# Sheet1.net
KiCad netlist of a schematic drawn in Altium Designer
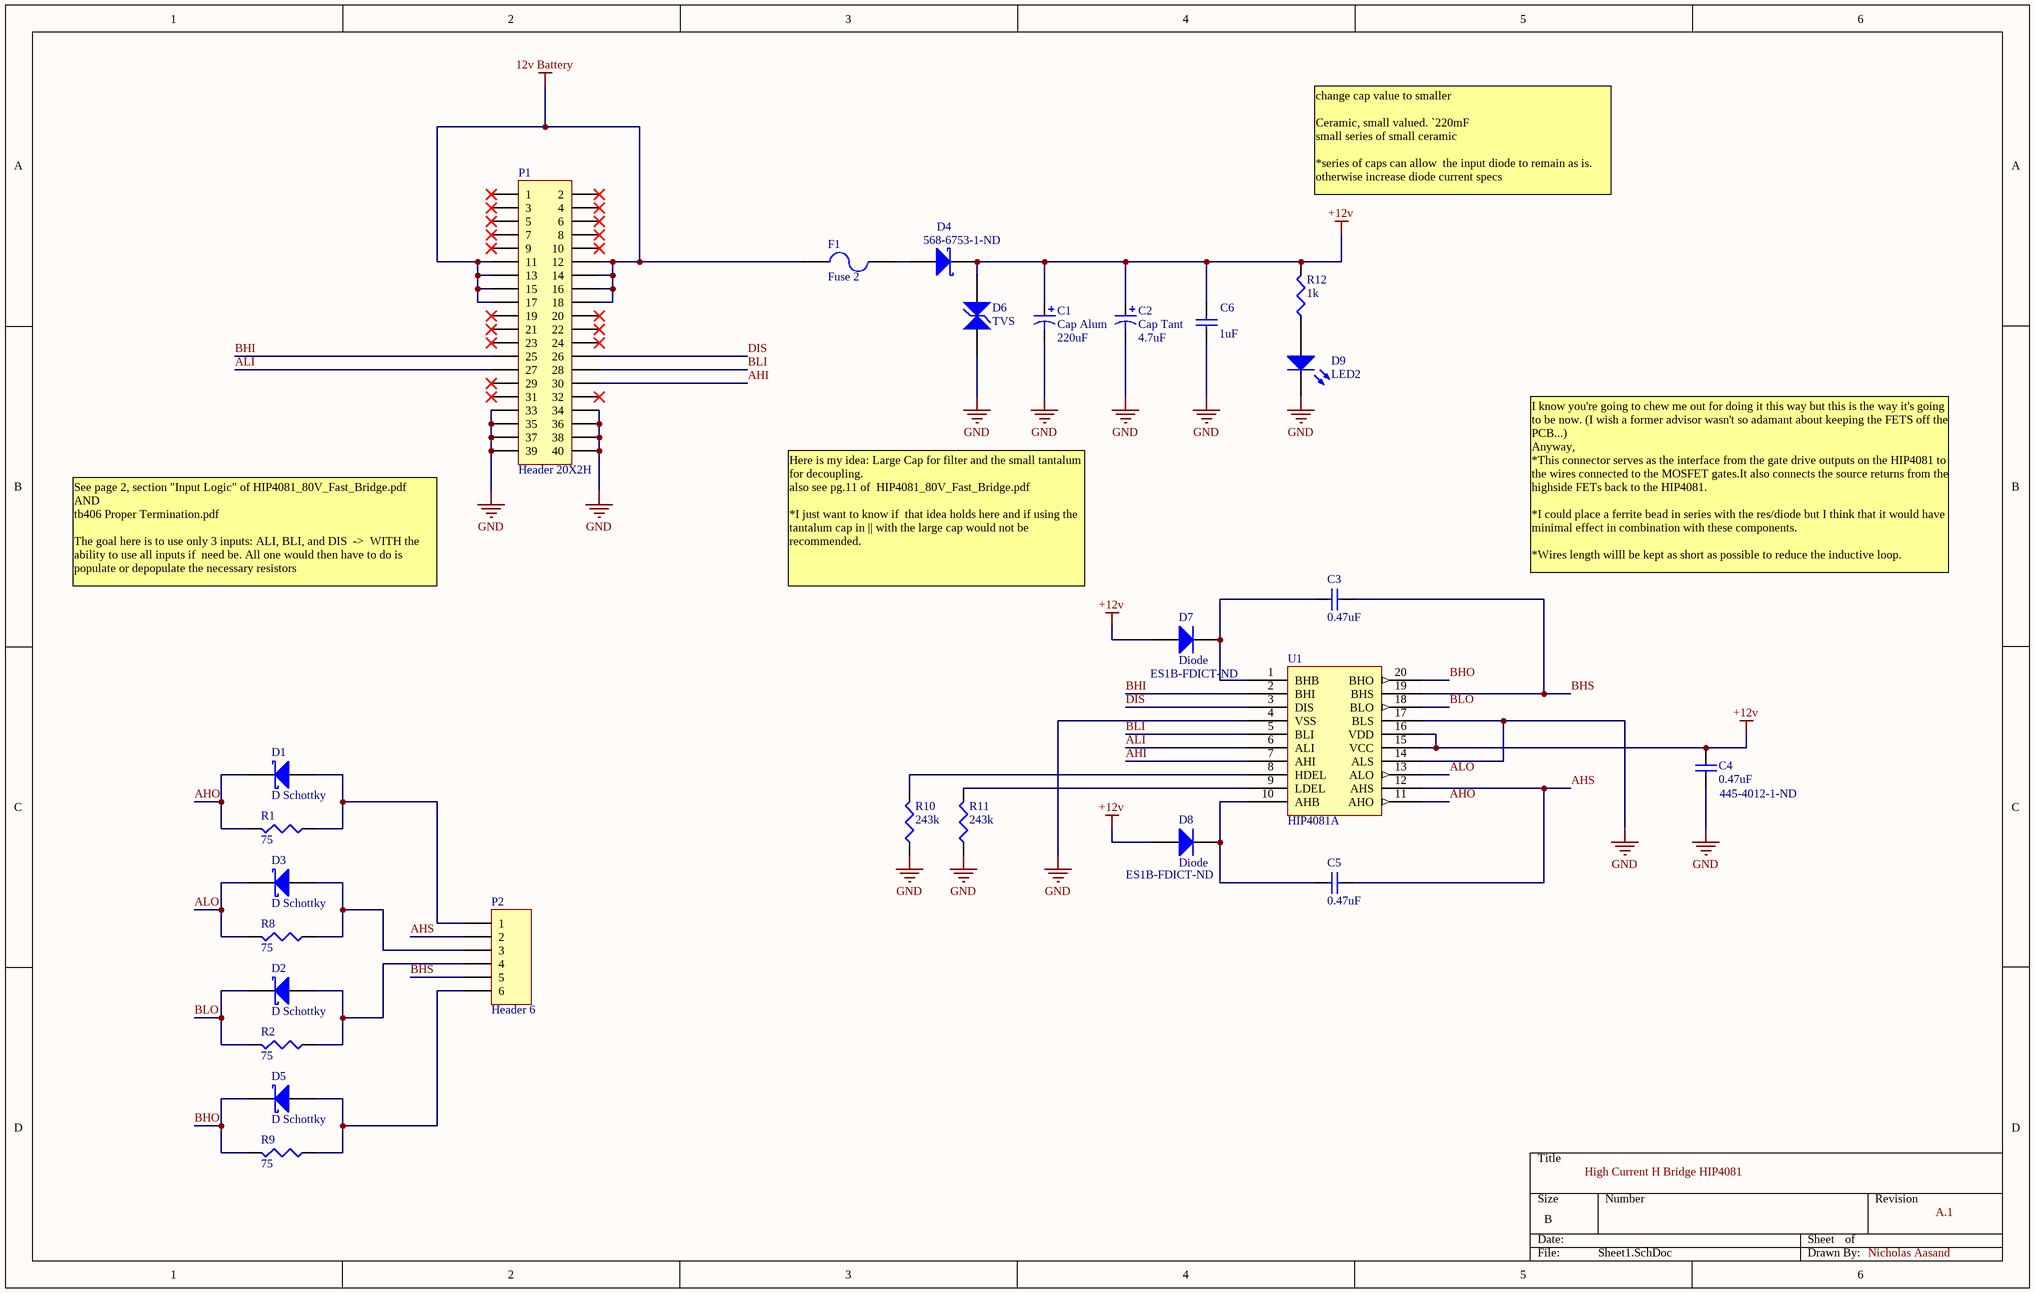
[diagram p0: Sheet1.SchDoc]

(export (version "E")
  (design (tool "Eeschema 10.0.6"))
  (components
    (comp (ref "C1")
      (value "Cap Alum")
      (footprint "CAPPR3.5-8x11.5")
      (description "Polarized Capacitor (Radial)")
      (fields (field (name "ALTIUM_VALUE") "220uF") (field (name "PUBLISHER") "Altium Limited"))
      (libsource (lib "Miscellaneous Devices") (part "Cap Pol1"))
    )
    (comp (ref "C2")
      (value "Cap Tant")
      (footprint "CP1206")
      (description "Polarized Capacitor (Surface Mount)")
      (fields (field (name "ALTIUM_VALUE") "4.7uF") (field (name "PUBLISHER") "Altium Limited"))
      (libsource (lib "Miscellaneous Devices") (part "Cap Pol3"))
    )
    (comp (ref "C3")
      (value "0.47uF")
      (footprint "C0805")
      (description "Capacitor (Semiconductor SIM Model)")
      (fields (field (name "Comment") "0805") (field (name "PUBLISHER") "Altium Limited"))
      (libsource (lib "Miscellaneous Devices") (part "Cap Semi"))
    )
    (comp (ref "C4")
      (value "0.47uF")
      (footprint "C1206")
      (description "Capacitor (Semiconductor SIM Model)")
      (fields
        (field (name "DIGIKEY") "445-4012-1-ND")
        (field (name "Comment") "0805")
        (field (name "PUBLISHER") "Altium Limited")
      )
      (libsource (lib "Miscellaneous Devices") (part "Cap Semi"))
    )
    (comp (ref "C5")
      (value "0.47uF")
      (footprint "C0805")
      (description "Capacitor (Semiconductor SIM Model)")
      (fields (field (name "Comment") "0805") (field (name "PUBLISHER") "Altium Limited"))
      (libsource (lib "Miscellaneous Devices") (part "Cap Semi"))
    )
    (comp (ref "C6")
      (value "1uF")
      (footprint "C0805")
      (description "Capacitor (Semiconductor SIM Model)")
      (fields (field (name "Comment") "0805") (field (name "PUBLISHER") "Altium Limited"))
      (libsource (lib "Miscellaneous Devices") (part "Cap Semi"))
    )
    (comp (ref "D1")
      (value "D Schottky")
      (footprint "SMB")
      (description "Schottky Diode")
      (fields (field (name "PUBLISHER") "Altium Limited"))
      (libsource (lib "Miscellaneous Devices") (part "D Schottky"))
    )
    (comp (ref "D2")
      (value "D Schottky")
      (footprint "SMB")
      (description "Schottky Diode")
      (fields (field (name "PUBLISHER") "Altium Limited"))
      (libsource (lib "Miscellaneous Devices") (part "D Schottky"))
    )
    (comp (ref "D3")
      (value "D Schottky")
      (footprint "SMB")
      (description "Schottky Diode")
      (fields (field (name "PUBLISHER") "Altium Limited"))
      (libsource (lib "Miscellaneous Devices") (part "D Schottky"))
    )
    (comp (ref "D4")
      (value "PMEG3030EP,115")
      (footprint "SOD128")
      (fields (field (name "DIGIKEY") "568-6753-1-ND") (field (name "PUBLISHER") "Altium Limited"))
      (libsource (lib "Miscellaneous Devices") (part "D Schottky"))
    )
    (comp (ref "D5")
      (value "D Schottky")
      (footprint "SMB")
      (description "Schottky Diode")
      (fields (field (name "PUBLISHER") "Altium Limited"))
      (libsource (lib "Miscellaneous Devices") (part "D Schottky"))
    )
    (comp (ref "D6")
      (value "TVS")
      (footprint "DSO-C2/X3.3")
      (description "Bi-directional TVS diode")
      (libsource (lib "Chips") (part "TVS_Bi"))
    )
    (comp (ref "D7")
      (value "Diode")
      (footprint "DSO-C2/G1.6")
      (description "Default Diode")
      (fields (field (name "DIGIKEY") "ES1B-FDICT-ND") (field (name "PUBLISHER") "Altium Limited"))
      (libsource (lib "Miscellaneous Devices") (part "Diode"))
    )
    (comp (ref "D8")
      (value "Diode")
      (footprint "DSO-C2/G1.6")
      (description "Default Diode")
      (fields (field (name "DIGIKEY") "ES1B-FDICT-ND") (field (name "PUBLISHER") "Altium Limited"))
      (libsource (lib "Miscellaneous Devices") (part "Diode"))
    )
    (comp (ref "D9")
      (value "LED2")
      (footprint "C0805")
      (description "Ultra Bright YELLOW ORANGE AlInGaP LED")
      (fields (field (name "PUBLISHER") "Altium Limited"))
      (libsource (lib "Miscellaneous Devices") (part "LED2"))
    )
    (comp (ref "F1")
      (value "Fuse 2")
      (footprint "3550-2 ATC Fuse Holder")
      (description "Fuse")
      (fields (field (name "PUBLISHER") "Altium Limited"))
      (libsource (lib "Miscellaneous Devices") (part "Fuse 2"))
    )
    (comp (ref "P1")
      (value "Header 20X2H")
      (footprint "HDR2X20H")
      (description "Header, 20-Pin, Dual row, Right Angle")
      (fields (field (name "PUBLISHER") "Altium Limited"))
      (libsource (lib "Miscellaneous Connectors") (part "Header 20X2H"))
    )
    (comp (ref "P2")
      (value "Header 6")
      (footprint "B6PS-VH")
      (description "Header, 6-Pin")
      (fields (field (name "PUBLISHER") "Altium Limited"))
      (libsource (lib "Miscellaneous Connectors") (part "Header 6"))
    )
    (comp (ref "R1")
      (value "75")
      (footprint "RESC3216N")
      (description "Resistor")
      (fields (field (name "Comment") "1206"))
      (libsource (lib "Miscellaneous Devices") (part "Res3"))
    )
    (comp (ref "R2")
      (value "75")
      (footprint "RESC3216N")
      (description "Resistor")
      (fields (field (name "Comment") "1206"))
      (libsource (lib "Miscellaneous Devices") (part "Res3"))
    )
    (comp (ref "R8")
      (value "75")
      (footprint "RESC3216N")
      (description "Resistor")
      (fields (field (name "Comment") "1206"))
      (libsource (lib "Miscellaneous Devices") (part "Res3"))
    )
    (comp (ref "R9")
      (value "75")
      (footprint "RESC3216N")
      (description "Resistor")
      (fields (field (name "Comment") "1206"))
      (libsource (lib "Miscellaneous Devices") (part "Res3"))
    )
    (comp (ref "R10")
      (value "243k")
      (footprint "C1206")
      (description "Resistor")
      (fields (field (name "Comment") "1206"))
      (libsource (lib "Miscellaneous Devices") (part "Res3"))
    )
    (comp (ref "R11")
      (value "243k")
      (footprint "C1206")
      (description "Resistor")
      (fields (field (name "Comment") "1206"))
      (libsource (lib "Miscellaneous Devices") (part "Res3"))
    )
    (comp (ref "R12")
      (value "1k")
      (footprint "RESC3216N")
      (description "Resistor")
      (fields (field (name "Comment") "1206"))
      (libsource (lib "Miscellaneous Devices") (part "Res3"))
    )
    (comp (ref "U1")
      (value "HIP4081A")
      (footprint "SOIC127P1030-20M")
      (description "80V/2.5A Peak, High Frequency Full Bridge FET Driver")
      (libsource (lib "HIP4081A") (part "HIP4081A"))
    )
  )
  (nets
    (net (code "1") (name "+12v") (class "Default")
      (node (ref "C1") (pin "1") (pinfunction "1_1") (pintype "passive"))
      (node (ref "C2") (pin "1") (pinfunction "1_1") (pintype "passive"))
      (node (ref "C4") (pin "1") (pinfunction "1_1") (pintype "passive"))
      (node (ref "C6") (pin "2") (pinfunction "2_2") (pintype "passive"))
      (node (ref "D4") (pin "2") (pinfunction "K_2") (pintype "passive"))
      (node (ref "D6") (pin "1") (pinfunction "1_1") (pintype "passive"))
      (node (ref "D7") (pin "1") (pinfunction "A_1") (pintype "passive"))
      (node (ref "D8") (pin "1") (pinfunction "A_1") (pintype "passive"))
      (node (ref "R12") (pin "2") (pinfunction "2_2") (pintype "passive"))
      (node (ref "U1") (pin "15") (pinfunction "VCC_15") (pintype "passive"))
      (node (ref "U1") (pin "16") (pinfunction "VDD_16") (pintype "passive"))
    )
    (net (code "2") (name "/AHI") (class "Default")
      (node (ref "P1") (pin "30") (pinfunction "30_30") (pintype "passive"))
      (node (ref "U1") (pin "7") (pinfunction "AHI_7") (pintype "passive"))
    )
    (net (code "3") (name "/AHO") (class "Default")
      (node (ref "D1") (pin "2") (pinfunction "K_2") (pintype "passive"))
      (node (ref "R1") (pin "2") (pinfunction "2_2") (pintype "passive"))
      (node (ref "U1") (pin "11") (pinfunction "AHO_11") (pintype "output"))
    )
    (net (code "4") (name "/AHS") (class "Default")
      (node (ref "C5") (pin "1") (pinfunction "1_1") (pintype "passive"))
      (node (ref "P2") (pin "2") (pinfunction "2_2") (pintype "passive"))
      (node (ref "U1") (pin "12") (pinfunction "AHS_12") (pintype "passive"))
    )
    (net (code "5") (name "/ALI") (class "Default")
      (node (ref "P1") (pin "27") (pinfunction "27_27") (pintype "passive"))
      (node (ref "U1") (pin "6") (pinfunction "ALI_6") (pintype "passive"))
    )
    (net (code "6") (name "/ALO") (class "Default")
      (node (ref "D3") (pin "2") (pinfunction "K_2") (pintype "passive"))
      (node (ref "R8") (pin "2") (pinfunction "2_2") (pintype "passive"))
      (node (ref "U1") (pin "13") (pinfunction "ALO_13") (pintype "output"))
    )
    (net (code "7") (name "/BHI") (class "Default")
      (node (ref "P1") (pin "25") (pinfunction "25_25") (pintype "passive"))
      (node (ref "U1") (pin "2") (pinfunction "BHI_2") (pintype "passive"))
    )
    (net (code "8") (name "/BHO") (class "Default")
      (node (ref "D5") (pin "2") (pinfunction "K_2") (pintype "passive"))
      (node (ref "R9") (pin "2") (pinfunction "2_2") (pintype "passive"))
      (node (ref "U1") (pin "20") (pinfunction "BHO_20") (pintype "output"))
    )
    (net (code "9") (name "/BHS") (class "Default")
      (node (ref "C3") (pin "1") (pinfunction "1_1") (pintype "passive"))
      (node (ref "P2") (pin "5") (pinfunction "5_5") (pintype "passive"))
      (node (ref "U1") (pin "19") (pinfunction "BHS_19") (pintype "passive"))
    )
    (net (code "10") (name "/BLI") (class "Default")
      (node (ref "P1") (pin "28") (pinfunction "28_28") (pintype "passive"))
      (node (ref "U1") (pin "5") (pinfunction "BLI_5") (pintype "passive"))
    )
    (net (code "11") (name "/BLO") (class "Default")
      (node (ref "D2") (pin "2") (pinfunction "K_2") (pintype "passive"))
      (node (ref "R2") (pin "2") (pinfunction "2_2") (pintype "passive"))
      (node (ref "U1") (pin "18") (pinfunction "BLO_18") (pintype "output"))
    )
    (net (code "12") (name "/DIS") (class "Default")
      (node (ref "P1") (pin "26") (pinfunction "26_26") (pintype "passive"))
      (node (ref "U1") (pin "3") (pinfunction "DIS_3") (pintype "passive"))
    )
    (net (code "13") (name "12v Battery") (class "Default")
      (node (ref "F1") (pin "1") (pinfunction "1_1") (pintype "passive"))
      (node (ref "P1") (pin "11") (pinfunction "11_11") (pintype "passive"))
      (node (ref "P1") (pin "12") (pinfunction "12_12") (pintype "passive"))
      (node (ref "P1") (pin "13") (pinfunction "13_13") (pintype "passive"))
      (node (ref "P1") (pin "14") (pinfunction "14_14") (pintype "passive"))
      (node (ref "P1") (pin "15") (pinfunction "15_15") (pintype "passive"))
      (node (ref "P1") (pin "16") (pinfunction "16_16") (pintype "passive"))
      (node (ref "P1") (pin "17") (pinfunction "17_17") (pintype "passive"))
      (node (ref "P1") (pin "18") (pinfunction "18_18") (pintype "passive"))
    )
    (net (code "14") (name "GND") (class "Default")
      (node (ref "C1") (pin "2") (pinfunction "2_2") (pintype "passive"))
      (node (ref "C2") (pin "2") (pinfunction "2_2") (pintype "passive"))
      (node (ref "C4") (pin "2") (pinfunction "2_2") (pintype "passive"))
      (node (ref "C6") (pin "1") (pinfunction "1_1") (pintype "passive"))
      (node (ref "D6") (pin "2") (pinfunction "2_2") (pintype "passive"))
      (node (ref "D9") (pin "2") (pinfunction "K_2") (pintype "passive"))
      (node (ref "P1") (pin "33") (pinfunction "33_33") (pintype "passive"))
      (node (ref "P1") (pin "34") (pinfunction "34_34") (pintype "passive"))
      (node (ref "P1") (pin "35") (pinfunction "35_35") (pintype "passive"))
      (node (ref "P1") (pin "36") (pinfunction "36_36") (pintype "passive"))
      (node (ref "P1") (pin "37") (pinfunction "37_37") (pintype "passive"))
      (node (ref "P1") (pin "38") (pinfunction "38_38") (pintype "passive"))
      (node (ref "P1") (pin "39") (pinfunction "39_39") (pintype "passive"))
      (node (ref "P1") (pin "40") (pinfunction "40_40") (pintype "passive"))
      (node (ref "R10") (pin "1") (pinfunction "1_1") (pintype "passive"))
      (node (ref "R11") (pin "1") (pinfunction "1_1") (pintype "passive"))
      (node (ref "U1") (pin "14") (pinfunction "ALS_14") (pintype "passive"))
      (node (ref "U1") (pin "17") (pinfunction "BLS_17") (pintype "passive"))
      (node (ref "U1") (pin "4") (pinfunction "VSS_4") (pintype "power_in"))
    )
    (net (code "15") (name "Net-(D1-A)") (class "Default")
      (node (ref "D1") (pin "1") (pinfunction "A_1") (pintype "passive"))
      (node (ref "P2") (pin "1") (pinfunction "1_1") (pintype "passive"))
      (node (ref "R1") (pin "1") (pinfunction "1_1") (pintype "passive"))
    )
    (net (code "16") (name "Net-(D2-A)") (class "Default")
      (node (ref "D2") (pin "1") (pinfunction "A_1") (pintype "passive"))
      (node (ref "P2") (pin "4") (pinfunction "4_4") (pintype "passive"))
      (node (ref "R2") (pin "1") (pinfunction "1_1") (pintype "passive"))
    )
    (net (code "17") (name "Net-(D3-A)") (class "Default")
      (node (ref "D3") (pin "1") (pinfunction "A_1") (pintype "passive"))
      (node (ref "P2") (pin "3") (pinfunction "3_3") (pintype "passive"))
      (node (ref "R8") (pin "1") (pinfunction "1_1") (pintype "passive"))
    )
    (net (code "18") (name "Net-(D4-A)") (class "Default")
      (node (ref "D4") (pin "1") (pinfunction "A_1") (pintype "passive"))
      (node (ref "F1") (pin "2") (pinfunction "2_2") (pintype "passive"))
    )
    (net (code "19") (name "Net-(D5-A)") (class "Default")
      (node (ref "D5") (pin "1") (pinfunction "A_1") (pintype "passive"))
      (node (ref "P2") (pin "6") (pinfunction "6_6") (pintype "passive"))
      (node (ref "R9") (pin "1") (pinfunction "1_1") (pintype "passive"))
    )
    (net (code "20") (name "Net-(D7-K)") (class "Default")
      (node (ref "C3") (pin "2") (pinfunction "2_2") (pintype "passive"))
      (node (ref "D7") (pin "2") (pinfunction "K_2") (pintype "passive"))
      (node (ref "U1") (pin "1") (pinfunction "BHB_1") (pintype "passive"))
    )
    (net (code "21") (name "Net-(D8-K)") (class "Default")
      (node (ref "C5") (pin "2") (pinfunction "2_2") (pintype "passive"))
      (node (ref "D8") (pin "2") (pinfunction "K_2") (pintype "passive"))
      (node (ref "U1") (pin "10") (pinfunction "AHB_10") (pintype "passive"))
    )
    (net (code "22") (name "Net-(D9-A)") (class "Default")
      (node (ref "D9") (pin "1") (pinfunction "A_1") (pintype "passive"))
      (node (ref "R12") (pin "1") (pinfunction "1_1") (pintype "passive"))
    )
    (net (code "23") (name "Net-(U1-HDEL)") (class "Default")
      (node (ref "R10") (pin "2") (pinfunction "2_2") (pintype "passive"))
      (node (ref "U1") (pin "8") (pinfunction "HDEL_8") (pintype "passive"))
    )
    (net (code "24") (name "Net-(U1-LDEL)") (class "Default")
      (node (ref "R11") (pin "2") (pinfunction "2_2") (pintype "passive"))
      (node (ref "U1") (pin "9") (pinfunction "LDEL_9") (pintype "passive"))
    )
    (net (code "25") (name "unconnected-(P1-Pad1)") (class "Default")
      (node (ref "P1") (pin "1") (pinfunction "1_1") (pintype "passive+no_connect"))
    )
    (net (code "26") (name "unconnected-(P1-Pad2)") (class "Default")
      (node (ref "P1") (pin "2") (pinfunction "2_2") (pintype "passive+no_connect"))
    )
    (net (code "27") (name "unconnected-(P1-Pad3)") (class "Default")
      (node (ref "P1") (pin "3") (pinfunction "3_3") (pintype "passive+no_connect"))
    )
    (net (code "28") (name "unconnected-(P1-Pad4)") (class "Default")
      (node (ref "P1") (pin "4") (pinfunction "4_4") (pintype "passive+no_connect"))
    )
    (net (code "29") (name "unconnected-(P1-Pad5)") (class "Default")
      (node (ref "P1") (pin "5") (pinfunction "5_5") (pintype "passive+no_connect"))
    )
    (net (code "30") (name "unconnected-(P1-Pad6)") (class "Default")
      (node (ref "P1") (pin "6") (pinfunction "6_6") (pintype "passive+no_connect"))
    )
    (net (code "31") (name "unconnected-(P1-Pad7)") (class "Default")
      (node (ref "P1") (pin "7") (pinfunction "7_7") (pintype "passive+no_connect"))
    )
    (net (code "32") (name "unconnected-(P1-Pad8)") (class "Default")
      (node (ref "P1") (pin "8") (pinfunction "8_8") (pintype "passive+no_connect"))
    )
    (net (code "33") (name "unconnected-(P1-Pad9)") (class "Default")
      (node (ref "P1") (pin "9") (pinfunction "9_9") (pintype "passive+no_connect"))
    )
    (net (code "34") (name "unconnected-(P1-Pad10)") (class "Default")
      (node (ref "P1") (pin "10") (pinfunction "10_10") (pintype "passive+no_connect"))
    )
    (net (code "35") (name "unconnected-(P1-Pad19)") (class "Default")
      (node (ref "P1") (pin "19") (pinfunction "19_19") (pintype "passive+no_connect"))
    )
    (net (code "36") (name "unconnected-(P1-Pad20)") (class "Default")
      (node (ref "P1") (pin "20") (pinfunction "20_20") (pintype "passive+no_connect"))
    )
    (net (code "37") (name "unconnected-(P1-Pad21)") (class "Default")
      (node (ref "P1") (pin "21") (pinfunction "21_21") (pintype "passive+no_connect"))
    )
    (net (code "38") (name "unconnected-(P1-Pad22)") (class "Default")
      (node (ref "P1") (pin "22") (pinfunction "22_22") (pintype "passive+no_connect"))
    )
    (net (code "39") (name "unconnected-(P1-Pad23)") (class "Default")
      (node (ref "P1") (pin "23") (pinfunction "23_23") (pintype "passive+no_connect"))
    )
    (net (code "40") (name "unconnected-(P1-Pad24)") (class "Default")
      (node (ref "P1") (pin "24") (pinfunction "24_24") (pintype "passive+no_connect"))
    )
    (net (code "41") (name "unconnected-(P1-Pad29)") (class "Default")
      (node (ref "P1") (pin "29") (pinfunction "29_29") (pintype "passive+no_connect"))
    )
    (net (code "42") (name "unconnected-(P1-Pad31)") (class "Default")
      (node (ref "P1") (pin "31") (pinfunction "31_31") (pintype "passive+no_connect"))
    )
    (net (code "43") (name "unconnected-(P1-Pad32)") (class "Default")
      (node (ref "P1") (pin "32") (pinfunction "32_32") (pintype "passive+no_connect"))
    )
  )
)
